# SupplyPower.net
KiCad netlist of a schematic drawn in Altium Designer
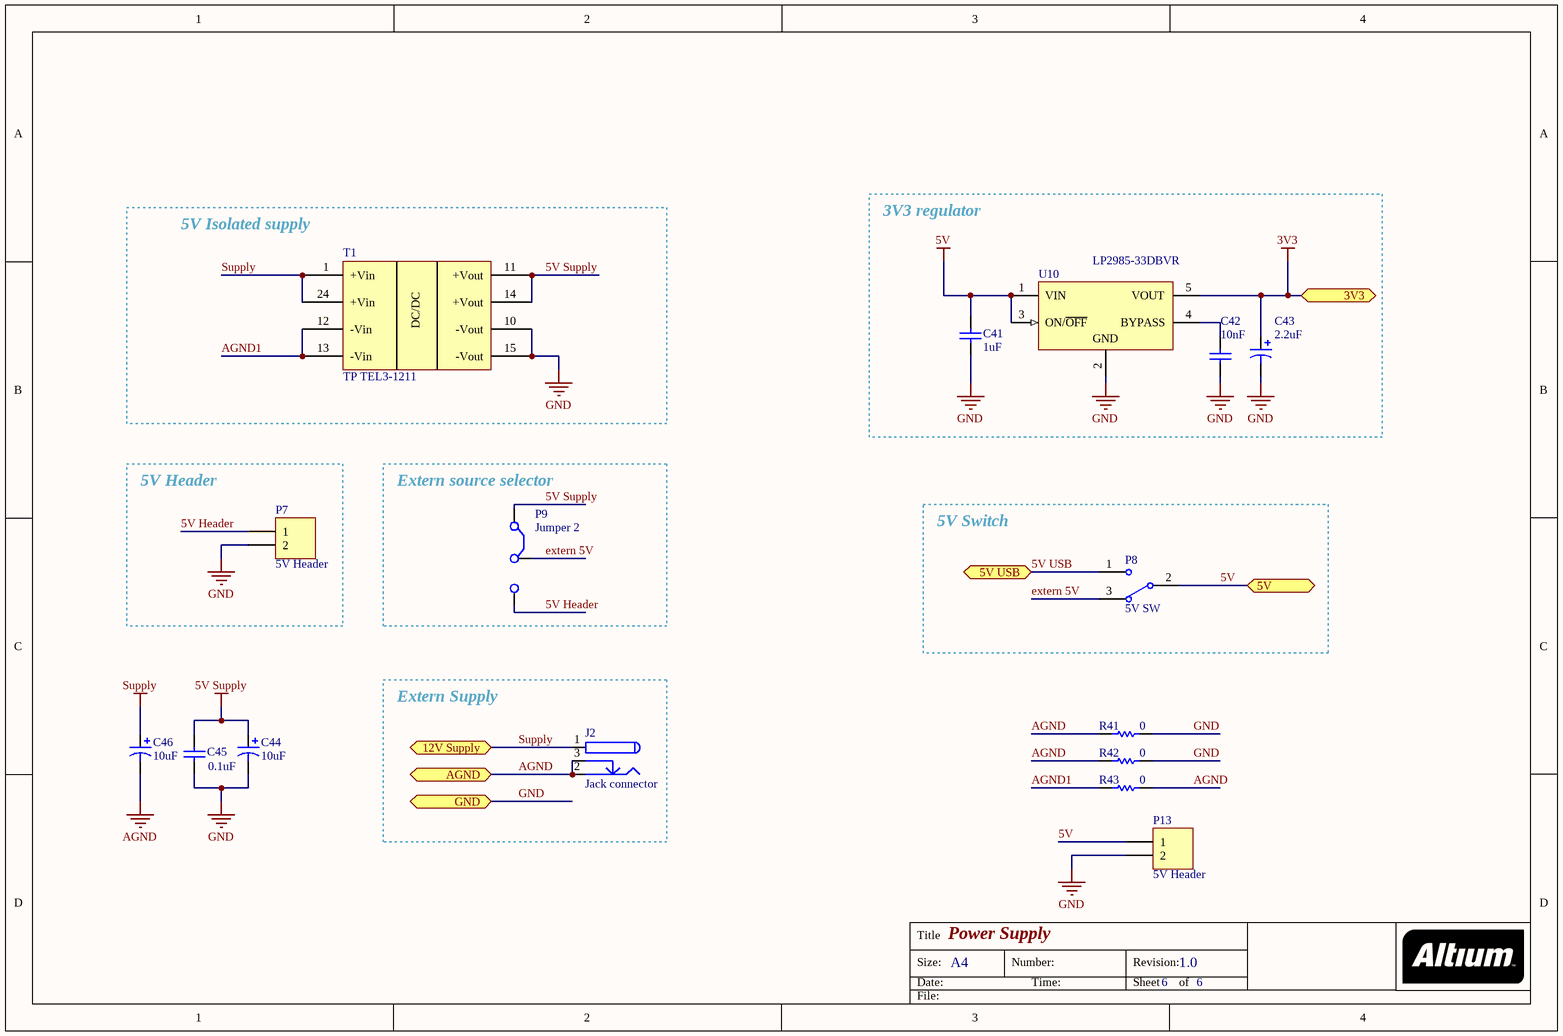
[diagram p0: SupplyPower.SchDoc]

(export (version "E")
  (design (tool "Eeschema 10.0.6"))
  (components
    (comp (ref "C41")
      (value "1uF")
      (footprint "0805")
      (description "Capacitor")
      (fields (field (name "Comment") "C1u") (field (name ".CREATOR") "SR"))
      (libsource (lib "Schlib") (part "C"))
    )
    (comp (ref "C42")
      (value "10nF")
      (footprint "C 1206")
      (description "Capacitor")
      (fields (field (name "Comment") "C10n") (field (name ".CREATOR") "SR"))
      (libsource (lib "CDR_SCH") (part "C"))
    )
    (comp (ref "C43")
      (value "2.2uF")
      (footprint "Tantalum")
      (description "Tantalum capacitor")
      (fields (field (name "Comment") "CT2.2u"))
      (libsource (lib "Schlib") (part "C Tantalum"))
    )
    (comp (ref "C44")
      (value "10uF")
      (footprint "Almn cap")
      (description "Capacitor polarzado")
      (fields (field (name "Comment") "C10u"))
      (libsource (lib "Schlib") (part "Capacitor pol"))
    )
    (comp (ref "C45")
      (value "0.1uF")
      (footprint "C 1206")
      (description "Capacitor")
      (fields (field (name "Comment") "C0.1u") (field (name ".CREATOR") "SR"))
      (libsource (lib "CDR_SCH") (part "C"))
    )
    (comp (ref "C46")
      (value "10uF")
      (footprint "CAP4x7x1.5mm")
      (description "Capacitor polarzado")
      (fields (field (name "Comment") "C10u"))
      (libsource (lib "Schlib") (part "Capacitor pol"))
    )
    (comp (ref "J2") (value "Jack connector") (libsource (lib "Schlib") (part "Jack connector")))
    (comp (ref "P7")
      (value "5V Header")
      (footprint "HDR1X2")
      (description "Header, 2-Pin")
      (fields (field (name "PUBLISHER") "Altium Limited"))
      (libsource (lib "Miscellaneous Connectors") (part "Header 2"))
    )
    (comp (ref "P8") (value "5V SW") (footprint "Toggle sw") (libsource (lib "Schlib") (part "toggle sw")))
    (comp (ref "P9") (value "Jumper 2") (footprint "Jumper 2") (libsource (lib "Schlib") (part "Jumper 2")))
    (comp (ref "P13")
      (value "5V Header")
      (footprint "HDR1X2")
      (description "Header, 2-Pin")
      (fields (field (name "PUBLISHER") "Altium Limited"))
      (libsource (lib "Miscellaneous Connectors") (part "Header 2"))
    )
    (comp (ref "R41")
      (value "0")
      (footprint "R 1206")
      (description "Resistencia")
      (fields (field (name "Comment") "R0") (field (name ".CREATOR") "SR"))
      (libsource (lib "CDR_SCH") (part "R"))
    )
    (comp (ref "R42")
      (value "0")
      (footprint "R 1206")
      (description "Resistencia")
      (fields (field (name "Comment") "R0") (field (name ".CREATOR") "SR"))
      (libsource (lib "CDR_SCH") (part "R"))
    )
    (comp (ref "R43")
      (value "0")
      (footprint "R 1206")
      (description "Resistencia")
      (fields (field (name "Comment") "R0") (field (name ".CREATOR") "SR"))
      (libsource (lib "CDR_SCH") (part "R"))
    )
    (comp (ref "T1") (value "TP TEL3-1211") (libsource (lib "Schlib") (part "TP TEL3-1211")))
    (comp (ref "U10")
      (value "LP2985-33DBVR")
      (footprint "TI-DBV5_N")
      (fields (field (name "MANUFACTURER") "Texas Instruments"))
      (libsource (lib "TI Power Management Linear Regulator Single Channel LDO (0-350mA)") (part "LP2985-10DBVR"))
    )
  )
  (nets
    (net (code "1") (name "/5V Header") (class "Default")
      (node (ref "P7") (pin "1") (pinfunction "1_1") (pintype "passive"))
      (node (ref "P9") (pin "3") (pinfunction "C3_3") (pintype "passive"))
    )
    (net (code "2") (name "/5V USB") (class "Default")
      (node (ref "P8") (pin "1") (pinfunction "1_1") (pintype "passive"))
    )
    (net (code "3") (name "/AGND1") (class "Default")
      (node (ref "R43") (pin "2") (pinfunction "2_2") (pintype "passive"))
      (node (ref "T1") (pin "12") (pinfunction "-Vin_12") (pintype "passive"))
      (node (ref "T1") (pin "13") (pinfunction "-Vin_13") (pintype "passive"))
    )
    (net (code "4") (name "/extern 5V") (class "Default")
      (node (ref "P8") (pin "3") (pinfunction "3_3") (pintype "passive"))
      (node (ref "P9") (pin "2") (pinfunction "C2_2") (pintype "passive"))
    )
    (net (code "5") (name "3V3") (class "Default")
      (node (ref "C43") (pin "1") (pinfunction "1_1") (pintype "passive"))
      (node (ref "U10") (pin "5") (pinfunction "VOUT_5") (pintype "power_in"))
    )
    (net (code "6") (name "5V") (class "Default")
      (node (ref "C41") (pin "1") (pinfunction "1_1") (pintype "passive"))
      (node (ref "P13") (pin "1") (pinfunction "1_1") (pintype "passive"))
      (node (ref "P8") (pin "2") (pinfunction "2_2") (pintype "passive"))
      (node (ref "U10") (pin "1") (pinfunction "VIN_1") (pintype "power_in"))
      (node (ref "U10") (pin "3") (pinfunction "ON/~{OFF}_3") (pintype "input"))
    )
    (net (code "7") (name "5V Supply") (class "Default")
      (node (ref "C44") (pin "1") (pinfunction "1_1") (pintype "passive"))
      (node (ref "C45") (pin "2") (pinfunction "2_2") (pintype "passive"))
      (node (ref "P9") (pin "1") (pinfunction "C1_1") (pintype "passive"))
      (node (ref "T1") (pin "11") (pinfunction "+Vout_11") (pintype "passive"))
      (node (ref "T1") (pin "14") (pinfunction "+Vout_14") (pintype "passive"))
    )
    (net (code "8") (name "AGND") (class "Default")
      (node (ref "C46") (pin "2") (pinfunction "2_2") (pintype "passive"))
      (node (ref "J2") (pin "2") (pinfunction "2_2") (pintype "power_in"))
      (node (ref "J2") (pin "3") (pinfunction "3_3") (pintype "power_in"))
      (node (ref "R41") (pin "2") (pinfunction "2_2") (pintype "passive"))
      (node (ref "R42") (pin "2") (pinfunction "2_2") (pintype "passive"))
      (node (ref "R43") (pin "1") (pinfunction "1_1") (pintype "passive"))
    )
    (net (code "9") (name "GND") (class "Default")
      (node (ref "C41") (pin "2") (pinfunction "2_2") (pintype "passive"))
      (node (ref "C42") (pin "2") (pinfunction "2_2") (pintype "passive"))
      (node (ref "C43") (pin "2") (pinfunction "2_2") (pintype "passive"))
      (node (ref "C44") (pin "2") (pinfunction "2_2") (pintype "passive"))
      (node (ref "C45") (pin "1") (pinfunction "1_1") (pintype "passive"))
      (node (ref "P13") (pin "2") (pinfunction "2_2") (pintype "passive"))
      (node (ref "P7") (pin "2") (pinfunction "2_2") (pintype "passive"))
      (node (ref "R41") (pin "1") (pinfunction "1_1") (pintype "passive"))
      (node (ref "R42") (pin "1") (pinfunction "1_1") (pintype "passive"))
      (node (ref "T1") (pin "10") (pinfunction "-Vout_10") (pintype "passive"))
      (node (ref "T1") (pin "15") (pinfunction "-Vout_15") (pintype "passive"))
      (node (ref "U10") (pin "2") (pinfunction "GND_2") (pintype "power_in"))
    )
    (net (code "10") (name "Net-(U10-BYPASS)") (class "Default")
      (node (ref "C42") (pin "1") (pinfunction "1_1") (pintype "passive"))
      (node (ref "U10") (pin "4") (pinfunction "BYPASS_4") (pintype "passive"))
    )
    (net (code "11") (name "Supply") (class "Default")
      (node (ref "C46") (pin "1") (pinfunction "1_1") (pintype "passive"))
      (node (ref "J2") (pin "1") (pinfunction "1_1") (pintype "power_in"))
      (node (ref "T1") (pin "1") (pinfunction "+Vin_1") (pintype "passive"))
      (node (ref "T1") (pin "24") (pinfunction "+Vin_24") (pintype "passive"))
    )
  )
)
